# MCU_POWER.net
KiCad netlist of a schematic drawn in Altium Designer
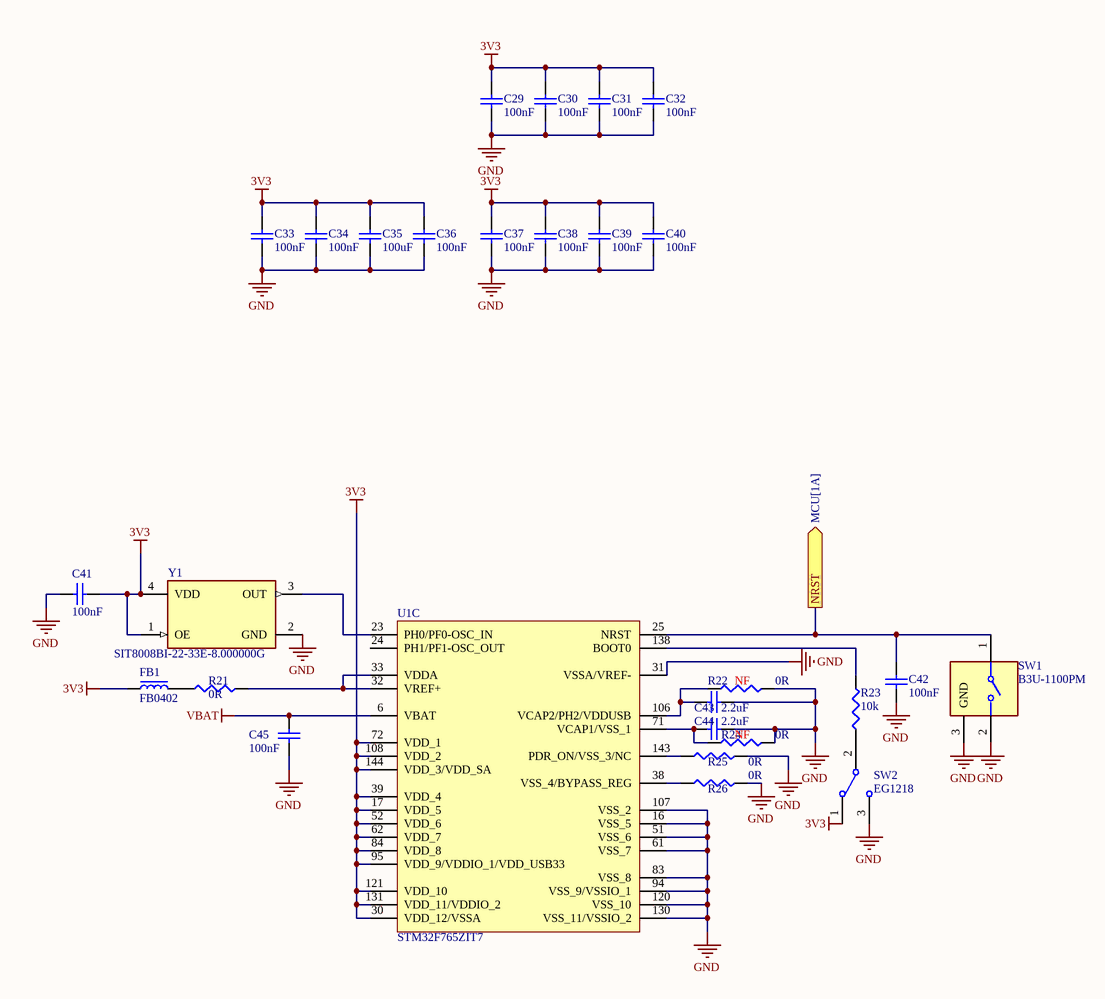
[diagram p0: MCU_POWER.SchDoc]

(export (version "E")
  (design (tool "Eeschema 10.0.6"))
  (components
    (comp (ref "C29")
      (value "100nF")
      (footprint "0402_C")
      (fields
        (field (name "MANUFACTURER") "Samsung Electro-Mechanics")
        (field (name "MANUFACTURER PART NUMBER") "CL05B104KO5NNNC")
        (field (name "TOLERANCE") "10%")
      )
      (libsource (lib "Flight_Computer1") (part "C_100nF_0402"))
    )
    (comp (ref "C30")
      (value "100nF")
      (footprint "0402_C")
      (fields
        (field (name "MANUFACTURER") "Samsung Electro-Mechanics")
        (field (name "MANUFACTURER PART NUMBER") "CL05B104KO5NNNC")
        (field (name "TOLERANCE") "10%")
      )
      (libsource (lib "Flight_Computer1") (part "C_100nF_0402"))
    )
    (comp (ref "C31")
      (value "100nF")
      (footprint "0402_C")
      (fields
        (field (name "MANUFACTURER") "Samsung Electro-Mechanics")
        (field (name "MANUFACTURER PART NUMBER") "CL05B104KO5NNNC")
        (field (name "TOLERANCE") "10%")
      )
      (libsource (lib "Flight_Computer1") (part "C_100nF_0402"))
    )
    (comp (ref "C32")
      (value "100nF")
      (footprint "0402_C")
      (fields
        (field (name "MANUFACTURER") "Samsung Electro-Mechanics")
        (field (name "MANUFACTURER PART NUMBER") "CL05B104KO5NNNC")
        (field (name "TOLERANCE") "10%")
      )
      (libsource (lib "Flight_Computer1") (part "C_100nF_0402"))
    )
    (comp (ref "C33")
      (value "100nF")
      (footprint "0402_C")
      (fields
        (field (name "MANUFACTURER") "Samsung Electro-Mechanics")
        (field (name "MANUFACTURER PART NUMBER") "CL05B104KO5NNNC")
        (field (name "TOLERANCE") "10%")
      )
      (libsource (lib "Flight_Computer1") (part "C_100nF_0402"))
    )
    (comp (ref "C34")
      (value "100nF")
      (footprint "0402_C")
      (fields
        (field (name "MANUFACTURER") "Samsung Electro-Mechanics")
        (field (name "MANUFACTURER PART NUMBER") "CL05B104KO5NNNC")
        (field (name "TOLERANCE") "10%")
      )
      (libsource (lib "Flight_Computer1") (part "C_100nF_0402"))
    )
    (comp (ref "C35")
      (value "100uF")
      (footprint "0402_C")
      (description "CAP CER 4.7UF 16V X5R 0402")
      (fields
        (field (name "MANUFACTURER") "Samsung")
        (field (name "MANUFACTURER PART NUMBER") "CL05A475MO5NUNC")
      )
      (libsource (lib "Flight_Computer1") (part "C_4.7uF_0402"))
    )
    (comp (ref "C36")
      (value "100nF")
      (footprint "0402_C")
      (fields
        (field (name "MANUFACTURER") "Samsung Electro-Mechanics")
        (field (name "MANUFACTURER PART NUMBER") "CL05B104KO5NNNC")
        (field (name "TOLERANCE") "10%")
      )
      (libsource (lib "Flight_Computer1") (part "C_100nF_0402"))
    )
    (comp (ref "C37")
      (value "100nF")
      (footprint "0402_C")
      (fields
        (field (name "MANUFACTURER") "Samsung Electro-Mechanics")
        (field (name "MANUFACTURER PART NUMBER") "CL05B104KO5NNNC")
        (field (name "TOLERANCE") "10%")
      )
      (libsource (lib "Flight_Computer1") (part "C_100nF_0402"))
    )
    (comp (ref "C38")
      (value "100nF")
      (footprint "0402_C")
      (fields
        (field (name "MANUFACTURER") "Samsung Electro-Mechanics")
        (field (name "MANUFACTURER PART NUMBER") "CL05B104KO5NNNC")
        (field (name "TOLERANCE") "10%")
      )
      (libsource (lib "Flight_Computer1") (part "C_100nF_0402"))
    )
    (comp (ref "C39")
      (value "100nF")
      (footprint "0402_C")
      (fields
        (field (name "MANUFACTURER") "Samsung Electro-Mechanics")
        (field (name "MANUFACTURER PART NUMBER") "CL05B104KO5NNNC")
        (field (name "TOLERANCE") "10%")
      )
      (libsource (lib "Flight_Computer1") (part "C_100nF_0402"))
    )
    (comp (ref "C40")
      (value "100nF")
      (footprint "0402_C")
      (fields
        (field (name "MANUFACTURER") "Samsung Electro-Mechanics")
        (field (name "MANUFACTURER PART NUMBER") "CL05B104KO5NNNC")
        (field (name "TOLERANCE") "10%")
      )
      (libsource (lib "Flight_Computer1") (part "C_100nF_0402"))
    )
    (comp (ref "C41")
      (value "100nF")
      (footprint "0402_C")
      (fields
        (field (name "MANUFACTURER") "Samsung Electro-Mechanics")
        (field (name "MANUFACTURER PART NUMBER") "CL05B104KO5NNNC")
        (field (name "TOLERANCE") "10%")
      )
      (libsource (lib "Flight_Computer1") (part "C_100nF_0402"))
    )
    (comp (ref "C42")
      (value "100nF")
      (footprint "0402_C")
      (fields
        (field (name "MANUFACTURER") "Samsung Electro-Mechanics")
        (field (name "MANUFACTURER PART NUMBER") "CL05B104KO5NNNC")
        (field (name "TOLERANCE") "10%")
      )
      (libsource (lib "Flight_Computer1") (part "C_100nF_0402"))
    )
    (comp (ref "C43")
      (value "2.2uF")
      (footprint "0402_C")
      (description "Ceramic Capacitor, Ceramic, 25V, 20% +Tol, 20% -Tol, X5R, 15% TC, 2.2uF, Surface Mount, 0402")
      (fields (field (name "LCSC PART #") "C723363") (field (name "MANUFACTURER") "Yageo Group"))
      (libsource (lib "Flight_Computer1") (part "C_2.2uF_0402_1"))
    )
    (comp (ref "C44")
      (value "2.2uF")
      (footprint "0402_C")
      (description "Ceramic Capacitor, Ceramic, 25V, 20% +Tol, 20% -Tol, X5R, 15% TC, 2.2uF, Surface Mount, 0402")
      (fields (field (name "LCSC PART #") "C723363") (field (name "MANUFACTURER") "Yageo Group"))
      (libsource (lib "Flight_Computer1") (part "C_2.2uF_0402_1"))
    )
    (comp (ref "C45")
      (value "100nF")
      (footprint "0402_C")
      (fields
        (field (name "MANUFACTURER") "Samsung Electro-Mechanics")
        (field (name "MANUFACTURER PART NUMBER") "CL05B104KO5NNNC")
        (field (name "TOLERANCE") "10%")
      )
      (libsource (lib "Flight_Computer1") (part "C_100nF_0402"))
    )
    (comp (ref "FB1")
      (value "FB0402")
      (footprint "0402_R")
      (description "Ferrite Beads Multi-Layer 600Ohm 25% 100MHz 300mA 520mOhm DCR 0402 Paper T/R")
      (fields
        (field (name "MANUFACTURER") "Murata Electronics")
        (field (name "MANUFACTURER PART NUMBER") "BLM15AG601SN1D")
      )
      (libsource (lib "Schlib1") (part "FB_0402"))
    )
    (comp (ref "R21")
      (value "0R")
      (footprint "0402_R")
      (description "GENERAL PURPOSE CHIP RESISTOR Metal Glaze/thick Film, 0.0625W, 0ohm, Surface Mount, 0402")
      (fields
        (field (name "MANUFACTURER") "Yageo Group")
        (field (name "MANUFACTURER PART NUMBER") "RC0402JR-070RL")
      )
      (libsource (lib "Schlib1") (part "R_0R_0402"))
    )
    (comp (ref "R22")
      (value "0R")
      (footprint "0402_R")
      (description "GENERAL PURPOSE CHIP RESISTOR Metal Glaze/thick Film, 0.0625W, 0ohm, Surface Mount, 0402")
      (fields
        (field (name "MANUFACTURER") "Yageo Group")
        (field (name "MANUFACTURER PART NUMBER") "RC0402JR-070RL")
      )
      (libsource (lib "Schlib1") (part "R_0R_0402"))
    )
    (comp (ref "R23")
      (value "10k")
      (footprint "0402_R")
      (description "RES SMD 10K OHM 0.1% 1/16W 0402")
      (fields (field (name "LCSC PART #") "C191915") (field (name "MANUFACTURER") "Yageo Group"))
      (libsource (lib "Flight_Computer1") (part "R_10k_0402"))
    )
    (comp (ref "R24")
      (value "0R")
      (footprint "0402_R")
      (description "GENERAL PURPOSE CHIP RESISTOR Metal Glaze/thick Film, 0.0625W, 0ohm, Surface Mount, 0402")
      (fields
        (field (name "MANUFACTURER") "Yageo Group")
        (field (name "MANUFACTURER PART NUMBER") "RC0402JR-070RL")
      )
      (libsource (lib "Schlib1") (part "R_0R_0402"))
    )
    (comp (ref "R25")
      (value "0R")
      (footprint "0402_R")
      (description "GENERAL PURPOSE CHIP RESISTOR Metal Glaze/thick Film, 0.0625W, 0ohm, Surface Mount, 0402")
      (fields
        (field (name "MANUFACTURER") "Yageo Group")
        (field (name "MANUFACTURER PART NUMBER") "RC0402JR-070RL")
      )
      (libsource (lib "Schlib1") (part "R_0R_0402"))
    )
    (comp (ref "R26")
      (value "0R")
      (footprint "0402_R")
      (description "GENERAL PURPOSE CHIP RESISTOR Metal Glaze/thick Film, 0.0625W, 0ohm, Surface Mount, 0402")
      (fields
        (field (name "MANUFACTURER") "Yageo Group")
        (field (name "MANUFACTURER PART NUMBER") "RC0402JR-070RL")
      )
      (libsource (lib "Schlib1") (part "R_0R_0402"))
    )
    (comp (ref "SW1")
      (value "B3U-1100PM")
      (footprint "FP-B3U-1100PM-MFG")
      (description "SWITCH TACTILE SPST-NO 0.05A 12V")
      (libsource (lib "Altium Content Vault") (part "6d7322ea62e06c21cb959ab9578dfa0"))
    )
    (comp (ref "SW2")
      (value "EG1218")
      (footprint "ESWI-EG1218_V")
      (description "Slide Switch, SPDT, 500 V, -20 to 70 degC, 3-Pin THD, RoHS, Bulk")
      (fields (field (name "MANUFACTURER") "E-Switch"))
      (libsource (lib "Americas - Purdue University - Purdue Space Program Hybrids") (part "SW-SPDT-3_B"))
    )
    (comp (ref "U1")
      (value "STM32F765ZIT7")
      (footprint "QFP50P2200X2200X160-144N")
      (description "Integrated Circuit")
      (fields (field (name "MOUSER PART NUMBER") "511-STM32F765ZIT7"))
      (libsource (lib "Flight_Computer1") (part "STM32F765ZIT7"))
    )
    (comp (ref "Y1")
      (value "SIT8008BI-22-33E-8.000000G")
      (footprint "FP-SiT8008-2-MFG")
      (description "MEMS OSC XO 8.0000MHZ H/LV-CMOS")
      (libsource (lib "Altium Content Vault") (part "cf86d2334cbefcf26da9ac2079652d4"))
    )
  )
  (nets
    (net (code "1") (name "/NRST") (class "Default")
      (node (ref "C42") (pin "1") (pinfunction "1_1") (pintype "passive"))
      (node (ref "SW1") (pin "1") (pinfunction "1_1") (pintype "passive"))
      (node (ref "U1") (pin "25") (pinfunction "NRST_25") (pintype "passive"))
    )
    (net (code "2") (name "3V3") (class "Default")
      (node (ref "C29") (pin "1") (pinfunction "1_1") (pintype "passive"))
      (node (ref "C30") (pin "1") (pinfunction "1_1") (pintype "passive"))
      (node (ref "C31") (pin "1") (pinfunction "1_1") (pintype "passive"))
      (node (ref "C32") (pin "1") (pinfunction "1_1") (pintype "passive"))
      (node (ref "C33") (pin "1") (pinfunction "1_1") (pintype "passive"))
      (node (ref "C34") (pin "1") (pinfunction "1_1") (pintype "passive"))
      (node (ref "C35") (pin "1") (pinfunction "1_1") (pintype "passive"))
      (node (ref "C36") (pin "1") (pinfunction "1_1") (pintype "passive"))
      (node (ref "C37") (pin "1") (pinfunction "1_1") (pintype "passive"))
      (node (ref "C38") (pin "1") (pinfunction "1_1") (pintype "passive"))
      (node (ref "C39") (pin "1") (pinfunction "1_1") (pintype "passive"))
      (node (ref "C40") (pin "1") (pinfunction "1_1") (pintype "passive"))
      (node (ref "C41") (pin "1") (pinfunction "1_1") (pintype "passive"))
      (node (ref "FB1") (pin "1") (pinfunction "1_1") (pintype "passive"))
      (node (ref "SW2") (pin "1") (pinfunction "1_1") (pintype "passive"))
      (node (ref "U1") (pin "108") (pinfunction "VDD_2_108") (pintype "passive"))
      (node (ref "U1") (pin "121") (pinfunction "VDD_10_121") (pintype "passive"))
      (node (ref "U1") (pin "131") (pinfunction "VDD_11/VDDIO_2_131") (pintype "passive"))
      (node (ref "U1") (pin "144") (pinfunction "VDD_3/VDD_SA_144") (pintype "passive"))
      (node (ref "U1") (pin "17") (pinfunction "VDD_5_17") (pintype "passive"))
      (node (ref "U1") (pin "30") (pinfunction "VDD_12/VSSA_30") (pintype "passive"))
      (node (ref "U1") (pin "39") (pinfunction "VDD_4_39") (pintype "passive"))
      (node (ref "U1") (pin "52") (pinfunction "VDD_6_52") (pintype "passive"))
      (node (ref "U1") (pin "62") (pinfunction "VDD_7_62") (pintype "passive"))
      (node (ref "U1") (pin "72") (pinfunction "VDD_1_72") (pintype "passive"))
      (node (ref "U1") (pin "84") (pinfunction "VDD_8_84") (pintype "passive"))
      (node (ref "U1") (pin "95") (pinfunction "VDD_9/VDDIO_1/VDD_USB33_95") (pintype "passive"))
      (node (ref "Y1") (pin "1") (pinfunction "OE_1") (pintype "input"))
      (node (ref "Y1") (pin "4") (pinfunction "VDD_4") (pintype "power_in"))
    )
    (net (code "3") (name "GND") (class "Default")
      (node (ref "C29") (pin "2") (pinfunction "2_2") (pintype "passive"))
      (node (ref "C30") (pin "2") (pinfunction "2_2") (pintype "passive"))
      (node (ref "C31") (pin "2") (pinfunction "2_2") (pintype "passive"))
      (node (ref "C32") (pin "2") (pinfunction "2_2") (pintype "passive"))
      (node (ref "C33") (pin "2") (pinfunction "2_2") (pintype "passive"))
      (node (ref "C34") (pin "2") (pinfunction "2_2") (pintype "passive"))
      (node (ref "C35") (pin "2") (pinfunction "2_2") (pintype "passive"))
      (node (ref "C36") (pin "2") (pinfunction "2_2") (pintype "passive"))
      (node (ref "C37") (pin "2") (pinfunction "2_2") (pintype "passive"))
      (node (ref "C38") (pin "2") (pinfunction "2_2") (pintype "passive"))
      (node (ref "C39") (pin "2") (pinfunction "2_2") (pintype "passive"))
      (node (ref "C40") (pin "2") (pinfunction "2_2") (pintype "passive"))
      (node (ref "C41") (pin "2") (pinfunction "2_2") (pintype "passive"))
      (node (ref "C42") (pin "2") (pinfunction "2_2") (pintype "passive"))
      (node (ref "C43") (pin "2") (pinfunction "2_2") (pintype "passive"))
      (node (ref "C44") (pin "2") (pinfunction "2_2") (pintype "passive"))
      (node (ref "C45") (pin "2") (pinfunction "2_2") (pintype "passive"))
      (node (ref "R22") (pin "2") (pinfunction "2_2") (pintype "passive"))
      (node (ref "R24") (pin "2") (pinfunction "2_2") (pintype "passive"))
      (node (ref "R25") (pin "2") (pinfunction "2_2") (pintype "passive"))
      (node (ref "R26") (pin "2") (pinfunction "2_2") (pintype "passive"))
      (node (ref "SW1") (pin "2") (pinfunction "2_2") (pintype "passive"))
      (node (ref "SW1") (pin "3") (pinfunction "GND_3") (pintype "power_in"))
      (node (ref "SW2") (pin "3") (pinfunction "3_3") (pintype "passive"))
      (node (ref "U1") (pin "107") (pinfunction "VSS_2_107") (pintype "passive"))
      (node (ref "U1") (pin "120") (pinfunction "VSS_10_120") (pintype "passive"))
      (node (ref "U1") (pin "130") (pinfunction "VSS_11/VSSIO_2_130") (pintype "passive"))
      (node (ref "U1") (pin "16") (pinfunction "VSS_5_16") (pintype "passive"))
      (node (ref "U1") (pin "31") (pinfunction "VSSA/VREF-_31") (pintype "passive"))
      (node (ref "U1") (pin "51") (pinfunction "VSS_6_51") (pintype "passive"))
      (node (ref "U1") (pin "61") (pinfunction "VSS_7_61") (pintype "passive"))
      (node (ref "U1") (pin "83") (pinfunction "VSS_8_83") (pintype "passive"))
      (node (ref "U1") (pin "94") (pinfunction "VSS_9/VSSIO_1_94") (pintype "passive"))
      (node (ref "Y1") (pin "2") (pinfunction "GND_2") (pintype "power_in"))
    )
    (net (code "4") (name "Net-(FB1-Pad2)") (class "Default")
      (node (ref "FB1") (pin "2") (pinfunction "2_2") (pintype "passive"))
      (node (ref "R21") (pin "1") (pinfunction "1_1") (pintype "passive"))
    )
    (net (code "5") (name "Net-(SW2-COM)") (class "Default")
      (node (ref "R23") (pin "2") (pinfunction "2_2") (pintype "passive"))
      (node (ref "SW2") (pin "2") (pinfunction "COM_2") (pintype "passive"))
    )
    (net (code "6") (name "Net-(U1C-BOOT0)") (class "Default")
      (node (ref "R23") (pin "1") (pinfunction "1_1") (pintype "passive"))
      (node (ref "U1") (pin "138") (pinfunction "BOOT0_138") (pintype "passive"))
    )
    (net (code "7") (name "Net-(U1C-PDR_ON{slash}VSS_3{slash}NC)") (class "Default")
      (node (ref "R25") (pin "1") (pinfunction "1_1") (pintype "passive"))
      (node (ref "U1") (pin "143") (pinfunction "PDR_ON/VSS_3/NC_143") (pintype "passive"))
    )
    (net (code "8") (name "Net-(U1C-PH0{slash}PF0-OSC_IN)") (class "Default")
      (node (ref "U1") (pin "23") (pinfunction "PH0/PF0-OSC_IN_23") (pintype "passive"))
      (node (ref "Y1") (pin "3") (pinfunction "OUT_3") (pintype "output"))
    )
    (net (code "9") (name "Net-(U1C-VCAP1{slash}VSS_1)") (class "Default")
      (node (ref "C44") (pin "1") (pinfunction "1_1") (pintype "passive"))
      (node (ref "R24") (pin "1") (pinfunction "1_1") (pintype "passive"))
      (node (ref "U1") (pin "71") (pinfunction "VCAP1/VSS_1_71") (pintype "passive"))
    )
    (net (code "10") (name "Net-(U1C-VCAP2{slash}PH2{slash}VDDUSB)") (class "Default")
      (node (ref "C43") (pin "1") (pinfunction "1_1") (pintype "passive"))
      (node (ref "R22") (pin "1") (pinfunction "1_1") (pintype "passive"))
      (node (ref "U1") (pin "106") (pinfunction "VCAP2/PH2/VDDUSB_106") (pintype "passive"))
    )
    (net (code "11") (name "Net-(U1C-VDDA)") (class "Default")
      (node (ref "R21") (pin "2") (pinfunction "2_2") (pintype "passive"))
      (node (ref "U1") (pin "32") (pinfunction "VREF+_32") (pintype "passive"))
      (node (ref "U1") (pin "33") (pinfunction "VDDA_33") (pintype "passive"))
    )
    (net (code "12") (name "Net-(U1C-VSS_4{slash}BYPASS_REG)") (class "Default")
      (node (ref "R26") (pin "1") (pinfunction "1_1") (pintype "passive"))
      (node (ref "U1") (pin "38") (pinfunction "VSS_4/BYPASS_REG_38") (pintype "passive"))
    )
    (net (code "13") (name "VBAT") (class "Default")
      (node (ref "C45") (pin "1") (pinfunction "1_1") (pintype "passive"))
      (node (ref "U1") (pin "6") (pinfunction "VBAT_6") (pintype "passive"))
    )
    (net (code "14") (name "unconnected-(U1C-PH1{slash}PF1-OSC_OUT-Pad24)") (class "Default")
      (node (ref "U1") (pin "24") (pinfunction "PH1/PF1-OSC_OUT_24") (pintype "passive"))
    )
  )
)
